# Knapper_og_leds.net
KiCad netlist of a schematic drawn in Altium Designer
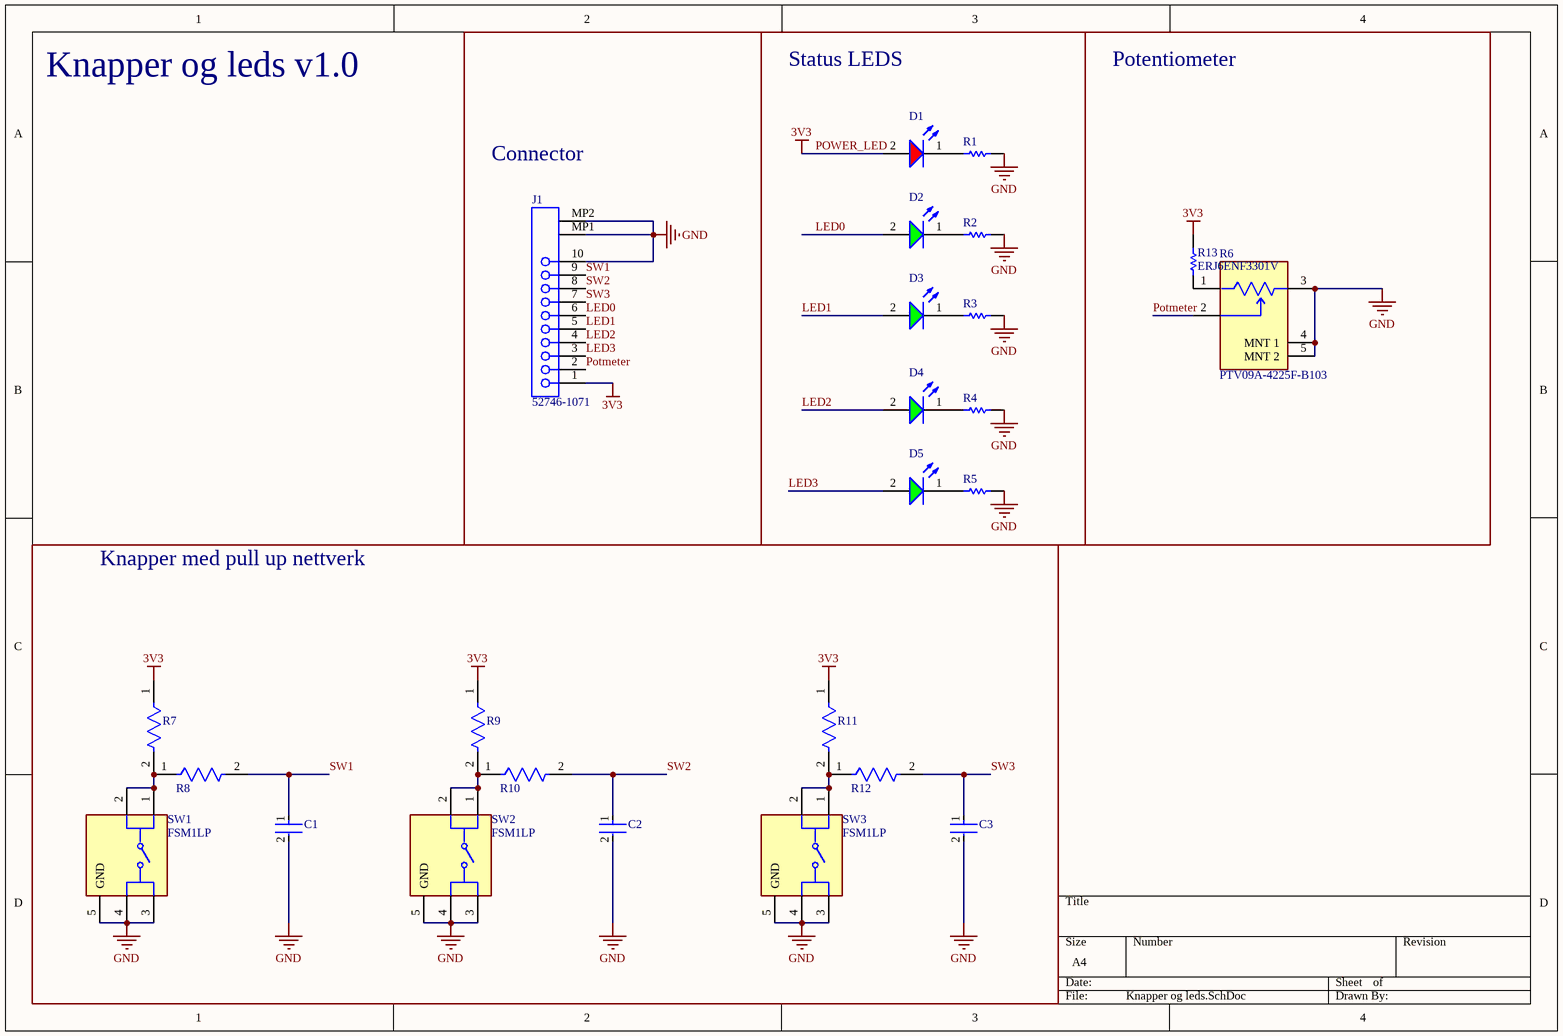
[diagram p0: Knapper og leds.SchDoc]

(export (version "E")
  (design (tool "Eeschema 10.0.6"))
  (components
    (comp (ref "C1")
      (value "CC0805KRX7R7BB104")
      (footprint "FP-CC0805-0_85-MFG")
      (description "CAP CER 0.1UF 16V X7R 0805")
      (fields
        (field (name "MANUFACTURER") "Yageo")
        (field (name "OCTOPART") "https://octopart.com/cc0805krx7r7bb104-yageo-39467769")
      )
      (libsource (lib "Altium Content Vault") (part "11868f565c42a9108669ba33697ecf6"))
    )
    (comp (ref "C2")
      (value "CC0805KRX7R7BB104")
      (footprint "FP-CC0805-0_85-MFG")
      (description "CAP CER 0.1UF 16V X7R 0805")
      (fields
        (field (name "MANUFACTURER") "Yageo")
        (field (name "OCTOPART") "https://octopart.com/cc0805krx7r7bb104-yageo-39467769")
      )
      (libsource (lib "Altium Content Vault") (part "11868f565c42a9108669ba33697ecf6"))
    )
    (comp (ref "C3")
      (value "CC0805KRX7R7BB104")
      (footprint "FP-CC0805-0_85-MFG")
      (description "CAP CER 0.1UF 16V X7R 0805")
      (fields
        (field (name "MANUFACTURER") "Yageo")
        (field (name "OCTOPART") "https://octopart.com/cc0805krx7r7bb104-yageo-39467769")
      )
      (libsource (lib "Altium Content Vault") (part "11868f565c42a9108669ba33697ecf6"))
    )
    (comp (ref "D1")
      (value "150080SS75000")
      (footprint "WL-SMCW_0805_150080xx75000")
      (libsource (lib "Altium Content Vault") (part "LED_Red_2A-1K"))
    )
    (comp (ref "D2")
      (value "150080VS75000")
      (footprint "WL-SMCW_0805_150080xx75000")
      (libsource (lib "Altium Content Vault") (part "LED_Green_2A-1K"))
    )
    (comp (ref "D3")
      (value "150080VS75000")
      (footprint "WL-SMCW_0805_150080xx75000")
      (libsource (lib "Altium Content Vault") (part "LED_Green_2A-1K"))
    )
    (comp (ref "D4")
      (value "150080VS75000")
      (footprint "WL-SMCW_0805_150080xx75000")
      (libsource (lib "Altium Content Vault") (part "LED_Green_2A-1K"))
    )
    (comp (ref "D5")
      (value "150080VS75000")
      (footprint "WL-SMCW_0805_150080xx75000")
      (libsource (lib "Altium Content Vault") (part "LED_Green_2A-1K"))
    )
    (comp (ref "J1")
      (value "52746-1071")
      (footprint "MOLX-52746-1071")
      (fields (field (name "MANUFACTURER") "Molex"))
      (libsource (lib "Altium Content Vault") (part "MOLX-52746-1071"))
    )
    (comp (ref "R1")
      (value "ERJ6ENF56R0V")
      (footprint "RESC2013X70X40NL20T20")
      (fields (field (name "MANUFACTURER") "Panasonic"))
      (libsource (lib "Altium Content Vault") (part "RES"))
    )
    (comp (ref "R2")
      (value "ERJ6ENF56R0V")
      (footprint "RESC2013X70X40NL20T20")
      (fields (field (name "MANUFACTURER") "Panasonic"))
      (libsource (lib "Altium Content Vault") (part "RES"))
    )
    (comp (ref "R3")
      (value "ERJ6ENF56R0V")
      (footprint "RESC2013X70X40NL20T20")
      (fields (field (name "MANUFACTURER") "Panasonic"))
      (libsource (lib "Altium Content Vault") (part "RES"))
    )
    (comp (ref "R4")
      (value "ERJ6ENF56R0V")
      (footprint "RESC2013X70X40NL20T20")
      (fields (field (name "MANUFACTURER") "Panasonic"))
      (libsource (lib "Altium Content Vault") (part "RES"))
    )
    (comp (ref "R5")
      (value "ERJ6ENF56R0V")
      (footprint "RESC2013X70X40NL20T20")
      (fields (field (name "MANUFACTURER") "Panasonic"))
      (libsource (lib "Altium Content Vault") (part "RES"))
    )
    (comp (ref "R6")
      (value "PTV09A-4225F-B103")
      (footprint "FP-PTV09A-4-MFG")
      (description "POT 10K OHM 1/20W CARBON LINEAR")
      (fields (field (name "TOLERANCE") "20%"))
      (libsource (lib "Altium Content Vault") (part "705d11b747745a787204d796a5f3d12"))
    )
    (comp (ref "R7")
      (value "CRCW080510K0FKEA")
      (footprint "FP-CRCW0805-e3-IPC_A")
      (description "RES Thick Film, 10kΩ, 1%, 0.125W, 100ppm/°C, 0805")
      (fields (field (name "TOLERANCE") "1%"))
      (libsource (lib "Altium Content Vault") (part "1029c3af85768c4190bb7ad29bc67b5"))
    )
    (comp (ref "R8")
      (value "CRCW080510K0FKEA")
      (footprint "FP-CRCW0805-e3-IPC_A")
      (description "RES Thick Film, 10kΩ, 1%, 0.125W, 100ppm/°C, 0805")
      (fields (field (name "TOLERANCE") "1%"))
      (libsource (lib "Altium Content Vault") (part "1029c3af85768c4190bb7ad29bc67b5"))
    )
    (comp (ref "R9")
      (value "CRCW080510K0FKEA")
      (footprint "FP-CRCW0805-e3-IPC_A")
      (description "RES Thick Film, 10kΩ, 1%, 0.125W, 100ppm/°C, 0805")
      (fields (field (name "TOLERANCE") "1%"))
      (libsource (lib "Altium Content Vault") (part "1029c3af85768c4190bb7ad29bc67b5"))
    )
    (comp (ref "R10")
      (value "CRCW080510K0FKEA")
      (footprint "FP-CRCW0805-e3-IPC_A")
      (description "RES Thick Film, 10kΩ, 1%, 0.125W, 100ppm/°C, 0805")
      (fields (field (name "TOLERANCE") "1%"))
      (libsource (lib "Altium Content Vault") (part "1029c3af85768c4190bb7ad29bc67b5"))
    )
    (comp (ref "R11")
      (value "CRCW080510K0FKEA")
      (footprint "FP-CRCW0805-e3-IPC_A")
      (description "RES Thick Film, 10kΩ, 1%, 0.125W, 100ppm/°C, 0805")
      (fields (field (name "TOLERANCE") "1%"))
      (libsource (lib "Altium Content Vault") (part "1029c3af85768c4190bb7ad29bc67b5"))
    )
    (comp (ref "R12")
      (value "CRCW080510K0FKEA")
      (footprint "FP-CRCW0805-e3-IPC_A")
      (description "RES Thick Film, 10kΩ, 1%, 0.125W, 100ppm/°C, 0805")
      (fields (field (name "TOLERANCE") "1%"))
      (libsource (lib "Altium Content Vault") (part "1029c3af85768c4190bb7ad29bc67b5"))
    )
    (comp (ref "R13")
      (value "ERJ6ENF3301V")
      (footprint "RESC2013X70X40ML20T20")
      (fields (field (name "MANUFACTURER") "Panasonic"))
      (libsource (lib "Altium Content Vault") (part "RES"))
    )
    (comp (ref "SW1")
      (value "FSM1LP")
      (footprint "FP-FSM1LP-MFG")
      (description "SWITCH TACTILE SPST-NO 0.05A 24V")
      (libsource (lib "Altium Content Vault") (part "3a9e64be5c1b186b34f28721102267a"))
    )
    (comp (ref "SW2")
      (value "FSM1LP")
      (footprint "FP-FSM1LP-MFG")
      (description "SWITCH TACTILE SPST-NO 0.05A 24V")
      (libsource (lib "Altium Content Vault") (part "3a9e64be5c1b186b34f28721102267a"))
    )
    (comp (ref "SW3")
      (value "FSM1LP")
      (footprint "FP-FSM1LP-MFG")
      (description "SWITCH TACTILE SPST-NO 0.05A 24V")
      (libsource (lib "Altium Content Vault") (part "3a9e64be5c1b186b34f28721102267a"))
    )
  )
  (nets
    (net (code "1") (name "/LED0") (class "Default")
      (node (ref "D2") (pin "2") (pinfunction "A_2") (pintype "passive"))
      (node (ref "J1") (pin "6") (pinfunction "6_6") (pintype "passive"))
    )
    (net (code "2") (name "/LED1") (class "Default")
      (node (ref "D3") (pin "2") (pinfunction "A_2") (pintype "passive"))
      (node (ref "J1") (pin "5") (pinfunction "5_5") (pintype "passive"))
    )
    (net (code "3") (name "/LED2") (class "Default")
      (node (ref "D4") (pin "2") (pinfunction "A_2") (pintype "passive"))
      (node (ref "J1") (pin "4") (pinfunction "4_4") (pintype "passive"))
    )
    (net (code "4") (name "/LED3") (class "Default")
      (node (ref "D5") (pin "2") (pinfunction "A_2") (pintype "passive"))
      (node (ref "J1") (pin "3") (pinfunction "3_3") (pintype "passive"))
    )
    (net (code "5") (name "/Potmeter") (class "Default")
      (node (ref "J1") (pin "2") (pinfunction "2_2") (pintype "passive"))
      (node (ref "R6") (pin "2") (pinfunction "2_2") (pintype "passive"))
    )
    (net (code "6") (name "/SW1") (class "Default")
      (node (ref "C1") (pin "1") (pinfunction "1_1") (pintype "passive"))
      (node (ref "J1") (pin "9") (pinfunction "9_9") (pintype "passive"))
      (node (ref "R8") (pin "2") (pinfunction "2_2") (pintype "passive"))
    )
    (net (code "7") (name "/SW2") (class "Default")
      (node (ref "C2") (pin "1") (pinfunction "1_1") (pintype "passive"))
      (node (ref "J1") (pin "8") (pinfunction "8_8") (pintype "passive"))
      (node (ref "R10") (pin "2") (pinfunction "2_2") (pintype "passive"))
    )
    (net (code "8") (name "/SW3") (class "Default")
      (node (ref "C3") (pin "1") (pinfunction "1_1") (pintype "passive"))
      (node (ref "J1") (pin "7") (pinfunction "7_7") (pintype "passive"))
      (node (ref "R12") (pin "2") (pinfunction "2_2") (pintype "passive"))
    )
    (net (code "9") (name "3V3") (class "Default")
      (node (ref "D1") (pin "2") (pinfunction "A_2") (pintype "passive"))
      (node (ref "J1") (pin "1") (pinfunction "1_1") (pintype "passive"))
      (node (ref "R11") (pin "1") (pinfunction "1_1") (pintype "passive"))
      (node (ref "R13") (pin "2") (pinfunction "2_2") (pintype "passive"))
      (node (ref "R7") (pin "1") (pinfunction "1_1") (pintype "passive"))
      (node (ref "R9") (pin "1") (pinfunction "1_1") (pintype "passive"))
    )
    (net (code "10") (name "GND") (class "Default")
      (node (ref "C1") (pin "2") (pinfunction "2_2") (pintype "passive"))
      (node (ref "C2") (pin "2") (pinfunction "2_2") (pintype "passive"))
      (node (ref "C3") (pin "2") (pinfunction "2_2") (pintype "passive"))
      (node (ref "J1") (pin "10") (pinfunction "10_10") (pintype "passive"))
      (node (ref "J1") (pin "MP1") (pinfunction "MP1_MP1") (pintype "passive"))
      (node (ref "J1") (pin "MP2") (pinfunction "MP2_MP2") (pintype "passive"))
      (node (ref "R1") (pin "2") (pinfunction "2_2") (pintype "passive"))
      (node (ref "R2") (pin "2") (pinfunction "2_2") (pintype "passive"))
      (node (ref "R3") (pin "2") (pinfunction "2_2") (pintype "passive"))
      (node (ref "R4") (pin "2") (pinfunction "2_2") (pintype "passive"))
      (node (ref "R5") (pin "2") (pinfunction "2_2") (pintype "passive"))
      (node (ref "R6") (pin "3") (pinfunction "3_3") (pintype "passive"))
      (node (ref "R6") (pin "4") (pinfunction "MNT_1_4") (pintype "passive"))
      (node (ref "R6") (pin "5") (pinfunction "MNT_2_5") (pintype "passive"))
      (node (ref "SW1") (pin "3") (pinfunction "3_3") (pintype "passive"))
      (node (ref "SW1") (pin "4") (pinfunction "4_4") (pintype "passive"))
      (node (ref "SW1") (pin "5") (pinfunction "GND_5") (pintype "power_in"))
      (node (ref "SW2") (pin "3") (pinfunction "3_3") (pintype "passive"))
      (node (ref "SW2") (pin "4") (pinfunction "4_4") (pintype "passive"))
      (node (ref "SW2") (pin "5") (pinfunction "GND_5") (pintype "power_in"))
      (node (ref "SW3") (pin "3") (pinfunction "3_3") (pintype "passive"))
      (node (ref "SW3") (pin "4") (pinfunction "4_4") (pintype "passive"))
      (node (ref "SW3") (pin "5") (pinfunction "GND_5") (pintype "power_in"))
    )
    (net (code "11") (name "Net-(D1-K)") (class "Default")
      (node (ref "D1") (pin "1") (pinfunction "K_1") (pintype "passive"))
      (node (ref "R1") (pin "1") (pinfunction "1_1") (pintype "passive"))
    )
    (net (code "12") (name "Net-(D2-K)") (class "Default")
      (node (ref "D2") (pin "1") (pinfunction "K_1") (pintype "passive"))
      (node (ref "R2") (pin "1") (pinfunction "1_1") (pintype "passive"))
    )
    (net (code "13") (name "Net-(D3-K)") (class "Default")
      (node (ref "D3") (pin "1") (pinfunction "K_1") (pintype "passive"))
      (node (ref "R3") (pin "1") (pinfunction "1_1") (pintype "passive"))
    )
    (net (code "14") (name "Net-(D4-K)") (class "Default")
      (node (ref "D4") (pin "1") (pinfunction "K_1") (pintype "passive"))
      (node (ref "R4") (pin "1") (pinfunction "1_1") (pintype "passive"))
    )
    (net (code "15") (name "Net-(D5-K)") (class "Default")
      (node (ref "D5") (pin "1") (pinfunction "K_1") (pintype "passive"))
      (node (ref "R5") (pin "1") (pinfunction "1_1") (pintype "passive"))
    )
    (net (code "16") (name "Net-(R7-Pad2)") (class "Default")
      (node (ref "R7") (pin "2") (pinfunction "2_2") (pintype "passive"))
      (node (ref "R8") (pin "1") (pinfunction "1_1") (pintype "passive"))
      (node (ref "SW1") (pin "1") (pinfunction "1_1") (pintype "passive"))
      (node (ref "SW1") (pin "2") (pinfunction "2_2") (pintype "passive"))
    )
    (net (code "17") (name "Net-(R10-Pad1)") (class "Default")
      (node (ref "R10") (pin "1") (pinfunction "1_1") (pintype "passive"))
      (node (ref "R9") (pin "2") (pinfunction "2_2") (pintype "passive"))
      (node (ref "SW2") (pin "1") (pinfunction "1_1") (pintype "passive"))
      (node (ref "SW2") (pin "2") (pinfunction "2_2") (pintype "passive"))
    )
    (net (code "18") (name "Net-(R11-Pad2)") (class "Default")
      (node (ref "R11") (pin "2") (pinfunction "2_2") (pintype "passive"))
      (node (ref "R12") (pin "1") (pinfunction "1_1") (pintype "passive"))
      (node (ref "SW3") (pin "1") (pinfunction "1_1") (pintype "passive"))
      (node (ref "SW3") (pin "2") (pinfunction "2_2") (pintype "passive"))
    )
    (net (code "19") (name "Net-(R13-Pad1)") (class "Default")
      (node (ref "R13") (pin "1") (pinfunction "1_1") (pintype "passive"))
      (node (ref "R6") (pin "1") (pinfunction "1_1") (pintype "passive"))
    )
  )
)
